# SCART_CONECTOR.net
KiCad netlist of a schematic drawn in EAGLE
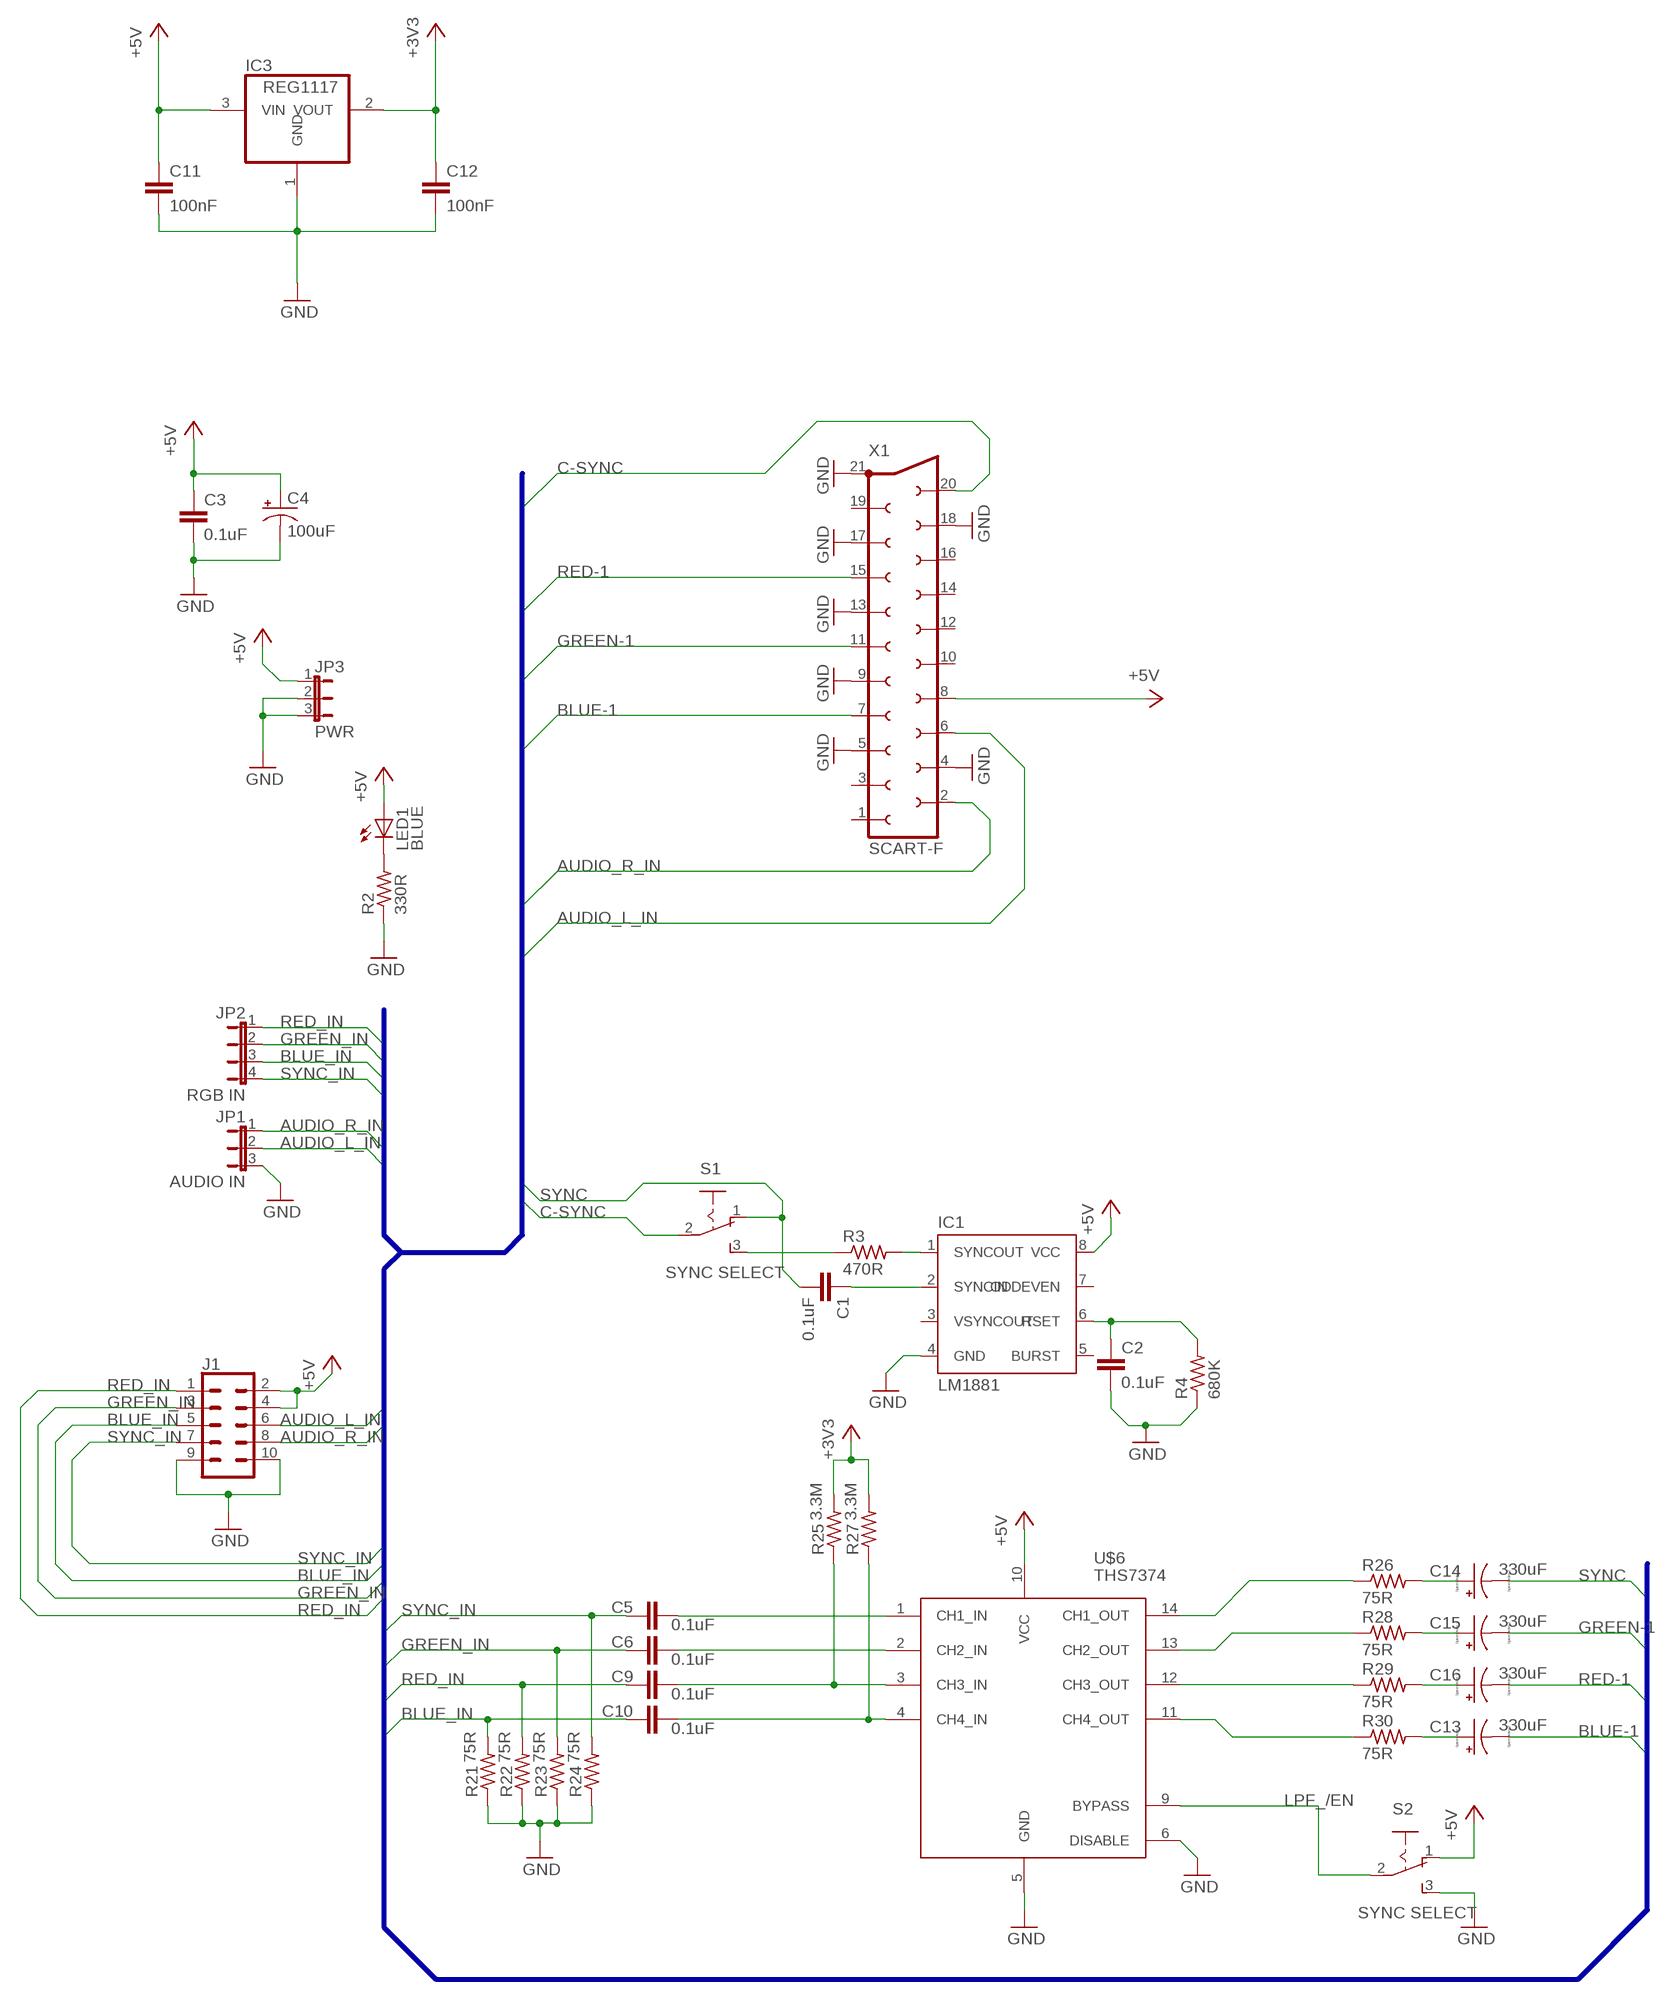
[diagram p0: schematic, sheet 1]

(export (version "E")
  (design (tool "Eeschema 10.0.6"))
  (components
    (comp (ref "C1")
      (value "0.1uF")
      (footprint "eagle-import:C7.5B3")
      (libsource (lib "eagle-import") (part "C7.5/3"))
    )
    (comp (ref "C2")
      (value "0.1uF")
      (footprint "eagle-import:C7.5B3")
      (libsource (lib "eagle-import") (part "C7.5/3"))
    )
    (comp (ref "C3")
      (value "0.1uF")
      (footprint "eagle-import:C7.5B3")
      (libsource (lib "eagle-import") (part "C7.5/3"))
    )
    (comp (ref "C4")
      (value "100uF")
      (footprint "eagle-import:E5-13")
      (libsource (lib "eagle-import") (part "CPOL-USE5-13"))
    )
    (comp (ref "C5")
      (value "0.1uF")
      (footprint "eagle-import:C050-025X075")
      (libsource (lib "eagle-import") (part "C-EU050-025X075"))
    )
    (comp (ref "C6")
      (value "0.1uF")
      (footprint "eagle-import:C050-025X075")
      (libsource (lib "eagle-import") (part "C-EU050-025X075"))
    )
    (comp (ref "C9")
      (value "0.1uF")
      (footprint "eagle-import:C050-025X075")
      (libsource (lib "eagle-import") (part "C-EU050-025X075"))
    )
    (comp (ref "C10")
      (value "0.1uF")
      (footprint "eagle-import:C050-025X075")
      (libsource (lib "eagle-import") (part "C-EU050-025X075"))
    )
    (comp (ref "C11")
      (value "100nF")
      (footprint "eagle-import:C075-032X103")
      (libsource (lib "eagle-import") (part "C-EU075-032X103"))
    )
    (comp (ref "C12")
      (value "100nF")
      (footprint "eagle-import:C075-032X103")
      (libsource (lib "eagle-import") (part "C-EU075-032X103"))
    )
    (comp (ref "C13")
      (value "330uF")
      (footprint "eagle-import:D_7343-31W")
      (libsource (lib "eagle-import") (part "resistor_CPOL-USD/7343-31W"))
    )
    (comp (ref "C14")
      (value "330uF")
      (footprint "eagle-import:D_7343-31W")
      (libsource (lib "eagle-import") (part "resistor_CPOL-USD/7343-31W"))
    )
    (comp (ref "C15")
      (value "330uF")
      (footprint "eagle-import:D_7343-31W")
      (libsource (lib "eagle-import") (part "resistor_CPOL-USD/7343-31W"))
    )
    (comp (ref "C16")
      (value "330uF")
      (footprint "eagle-import:D_7343-31W")
      (libsource (lib "eagle-import") (part "resistor_CPOL-USD/7343-31W"))
    )
    (comp (ref "IC1")
      (value "LM1881")
      (footprint "eagle-import:DIL08")
      (libsource (lib "eagle-import") (part "LM1881"))
    )
    (comp (ref "IC3")
      (value "REG1117")
      (footprint "eagle-import:SOT223")
      (libsource (lib "eagle-import") (part "REG1117"))
    )
    (comp (ref "J1")
      (value "CONN_05X2SHD-NS")
      (footprint "eagle-import:2X5-SHROUDED-NS")
      (libsource (lib "eagle-import") (part "CONN_05X2SHD-NS"))
    )
    (comp (ref "JP1")
      (value "AUDIO IN")
      (footprint "eagle-import:JP2")
      (libsource (lib "eagle-import") (part "JP2E"))
    )
    (comp (ref "JP2")
      (value "RGB IN")
      (footprint "eagle-import:JP4")
      (libsource (lib "eagle-import") (part "JP4E"))
    )
    (comp (ref "JP3")
      (value "PWR")
      (footprint "eagle-import:JP2")
      (libsource (lib "eagle-import") (part "JP2E"))
    )
    (comp (ref "LED1")
      (value "BLUE")
      (footprint "eagle-import:LED5MM")
      (libsource (lib "eagle-import") (part "LED5MM"))
    )
    (comp (ref "R2")
      (value "330R")
      (footprint "eagle-import:0204_7")
      (libsource (lib "eagle-import") (part "R-US_0204/7"))
    )
    (comp (ref "R3")
      (value "470R")
      (footprint "eagle-import:0204_7")
      (libsource (lib "eagle-import") (part "R-US_0204/7"))
    )
    (comp (ref "R4")
      (value "680K")
      (footprint "eagle-import:0204_7")
      (libsource (lib "eagle-import") (part "R-US_0204/7"))
    )
    (comp (ref "R21")
      (value "75R")
      (footprint "eagle-import:0204V")
      (libsource (lib "eagle-import") (part "R-US_0204/2V"))
    )
    (comp (ref "R22")
      (value "75R")
      (footprint "eagle-import:0204V")
      (libsource (lib "eagle-import") (part "R-US_0204/2V"))
    )
    (comp (ref "R23")
      (value "75R")
      (footprint "eagle-import:0204V")
      (libsource (lib "eagle-import") (part "R-US_0204/2V"))
    )
    (comp (ref "R24")
      (value "75R")
      (footprint "eagle-import:0204V")
      (libsource (lib "eagle-import") (part "R-US_0204/2V"))
    )
    (comp (ref "R25")
      (value "3.3M")
      (footprint "eagle-import:0204_7")
      (libsource (lib "eagle-import") (part "R-US_0204/7"))
    )
    (comp (ref "R26")
      (value "75R")
      (footprint "eagle-import:0204_7")
      (libsource (lib "eagle-import") (part "R-US_0204/7"))
    )
    (comp (ref "R27")
      (value "3.3M")
      (footprint "eagle-import:0204_7")
      (libsource (lib "eagle-import") (part "R-US_0204/7"))
    )
    (comp (ref "R28")
      (value "75R")
      (footprint "eagle-import:0204_7")
      (libsource (lib "eagle-import") (part "R-US_0204/7"))
    )
    (comp (ref "R29")
      (value "75R")
      (footprint "eagle-import:0204_7")
      (libsource (lib "eagle-import") (part "R-US_0204/7"))
    )
    (comp (ref "R30")
      (value "75R")
      (footprint "eagle-import:0204_7")
      (libsource (lib "eagle-import") (part "R-US_0204/7"))
    )
    (comp (ref "S1")
      (value "SYNC SELECT")
      (footprint "eagle-import:255SB")
      (libsource (lib "eagle-import") (part "255SB"))
    )
    (comp (ref "S2")
      (value "SYNC SELECT")
      (footprint "eagle-import:255SB")
      (libsource (lib "eagle-import") (part "255SB"))
    )
    (comp (ref "U$6")
      (value "THS7374")
      (footprint "eagle-import:TSSOP-14")
      (libsource (lib "eagle-import") (part "THS7374"))
    )
    (comp (ref "X1")
      (value "SCART-F")
      (footprint "eagle-import:SCART-F")
      (libsource (lib "eagle-import") (part "SCART-F"))
    )
  )
  (nets
    (net (code "1") (name "+3V3") (class "Default")
      (node (ref "C12") (pin "1") (pinfunction "1_1") (pintype "passive"))
      (node (ref "IC3") (pin "2") (pinfunction "VOUT_2") (pintype "output"))
      (node (ref "R25") (pin "2") (pinfunction "2_2") (pintype "passive"))
      (node (ref "R27") (pin "2") (pinfunction "2_2") (pintype "passive"))
    )
    (net (code "2") (name "+5V") (class "Default")
      (node (ref "C11") (pin "1") (pinfunction "1_1") (pintype "passive"))
      (node (ref "C3") (pin "1") (pinfunction "1_1") (pintype "passive"))
      (node (ref "C4") (pin "+") (pinfunction "+_+") (pintype "passive"))
      (node (ref "IC1") (pin "8") (pinfunction "VCC_8") (pintype "power_in"))
      (node (ref "IC3") (pin "3") (pinfunction "VIN_3") (pintype "input"))
      (node (ref "J1") (pin "2") (pinfunction "2_2") (pintype "passive"))
      (node (ref "J1") (pin "4") (pinfunction "4_4") (pintype "passive"))
      (node (ref "JP3") (pin "1") (pinfunction "1_1") (pintype "passive"))
      (node (ref "LED1") (pin "A") (pinfunction "A_A") (pintype "passive"))
      (node (ref "S2") (pin "1") (pinfunction "O_1") (pintype "passive"))
      (node (ref "U$6") (pin "10") (pinfunction "VCC_10") (pintype "power_in"))
      (node (ref "X1") (pin "8") (pinfunction "8_8") (pintype "passive"))
    )
    (net (code "3") (name "/AUDIO_L_IN") (class "Default")
      (node (ref "J1") (pin "6") (pinfunction "6_6") (pintype "passive"))
      (node (ref "JP1") (pin "2") (pinfunction "2_2") (pintype "passive"))
      (node (ref "X1") (pin "6") (pinfunction "6_6") (pintype "passive"))
    )
    (net (code "4") (name "/AUDIO_R_IN") (class "Default")
      (node (ref "J1") (pin "8") (pinfunction "8_8") (pintype "passive"))
      (node (ref "JP1") (pin "1") (pinfunction "1_1") (pintype "passive"))
      (node (ref "X1") (pin "2") (pinfunction "2_2") (pintype "passive"))
    )
    (net (code "5") (name "/BLUE-1") (class "Default")
      (node (ref "C13") (pin "-") (pinfunction "-_-") (pintype "passive"))
      (node (ref "X1") (pin "7") (pinfunction "7_7") (pintype "passive"))
    )
    (net (code "6") (name "/BLUE_IN") (class "Default")
      (node (ref "C10") (pin "1") (pinfunction "1_1") (pintype "passive"))
      (node (ref "J1") (pin "5") (pinfunction "5_5") (pintype "passive"))
      (node (ref "JP2") (pin "3") (pinfunction "3_3") (pintype "passive"))
      (node (ref "R21") (pin "2") (pinfunction "2_2") (pintype "passive"))
    )
    (net (code "7") (name "/C-SYNC") (class "Default")
      (node (ref "S1") (pin "2") (pinfunction "P_2") (pintype "passive"))
      (node (ref "X1") (pin "20") (pinfunction "20_20") (pintype "passive"))
    )
    (net (code "8") (name "/GREEN-1") (class "Default")
      (node (ref "C15") (pin "-") (pinfunction "-_-") (pintype "passive"))
      (node (ref "X1") (pin "11") (pinfunction "11_11") (pintype "passive"))
    )
    (net (code "9") (name "/GREEN_IN") (class "Default")
      (node (ref "C6") (pin "1") (pinfunction "1_1") (pintype "passive"))
      (node (ref "J1") (pin "3") (pinfunction "3_3") (pintype "passive"))
      (node (ref "JP2") (pin "2") (pinfunction "2_2") (pintype "passive"))
      (node (ref "R23") (pin "2") (pinfunction "2_2") (pintype "passive"))
    )
    (net (code "10") (name "/LPF_{slash}EN") (class "Default")
      (node (ref "S2") (pin "2") (pinfunction "P_2") (pintype "passive"))
      (node (ref "U$6") (pin "9") (pinfunction "BYPASS_9") (pintype "input"))
    )
    (net (code "11") (name "/RED-1") (class "Default")
      (node (ref "C16") (pin "-") (pinfunction "-_-") (pintype "passive"))
      (node (ref "X1") (pin "15") (pinfunction "15_15") (pintype "passive"))
    )
    (net (code "12") (name "/RED_IN") (class "Default")
      (node (ref "C9") (pin "1") (pinfunction "1_1") (pintype "passive"))
      (node (ref "J1") (pin "1") (pinfunction "1_1") (pintype "passive"))
      (node (ref "JP2") (pin "1") (pinfunction "1_1") (pintype "passive"))
      (node (ref "R22") (pin "2") (pinfunction "2_2") (pintype "passive"))
    )
    (net (code "13") (name "/SYNC") (class "Default")
      (node (ref "C1") (pin "2") (pinfunction "2_2") (pintype "passive"))
      (node (ref "C14") (pin "-") (pinfunction "-_-") (pintype "passive"))
      (node (ref "S1") (pin "1") (pinfunction "O_1") (pintype "passive"))
    )
    (net (code "14") (name "/SYNC_IN") (class "Default")
      (node (ref "C5") (pin "1") (pinfunction "1_1") (pintype "passive"))
      (node (ref "J1") (pin "7") (pinfunction "7_7") (pintype "passive"))
      (node (ref "JP2") (pin "4") (pinfunction "4_4") (pintype "passive"))
      (node (ref "R24") (pin "2") (pinfunction "2_2") (pintype "passive"))
    )
    (net (code "15") (name "GND") (class "Default")
      (node (ref "C11") (pin "2") (pinfunction "2_2") (pintype "passive"))
      (node (ref "C12") (pin "2") (pinfunction "2_2") (pintype "passive"))
      (node (ref "C2") (pin "2") (pinfunction "2_2") (pintype "passive"))
      (node (ref "C3") (pin "2") (pinfunction "2_2") (pintype "passive"))
      (node (ref "C4") (pin "-") (pinfunction "-_-") (pintype "passive"))
      (node (ref "IC1") (pin "4") (pinfunction "GND_4") (pintype "power_in"))
      (node (ref "IC3") (pin "1") (pinfunction "GND_1") (pintype "power_in"))
      (node (ref "J1") (pin "10") (pinfunction "10_10") (pintype "passive"))
      (node (ref "J1") (pin "9") (pinfunction "9_9") (pintype "passive"))
      (node (ref "JP1") (pin "3") (pinfunction "3_3") (pintype "passive"))
      (node (ref "JP3") (pin "2") (pinfunction "2_2") (pintype "passive"))
      (node (ref "JP3") (pin "3") (pinfunction "3_3") (pintype "passive"))
      (node (ref "R2") (pin "1") (pinfunction "1_1") (pintype "passive"))
      (node (ref "R21") (pin "1") (pinfunction "1_1") (pintype "passive"))
      (node (ref "R22") (pin "1") (pinfunction "1_1") (pintype "passive"))
      (node (ref "R23") (pin "1") (pinfunction "1_1") (pintype "passive"))
      (node (ref "R24") (pin "1") (pinfunction "1_1") (pintype "passive"))
      (node (ref "R4") (pin "1") (pinfunction "1_1") (pintype "passive"))
      (node (ref "S2") (pin "3") (pinfunction "S_3") (pintype "passive"))
      (node (ref "U$6") (pin "5") (pinfunction "GND_5") (pintype "power_in"))
      (node (ref "U$6") (pin "6") (pinfunction "DISABLE_6") (pintype "input"))
      (node (ref "X1") (pin "13") (pinfunction "13_13") (pintype "passive"))
      (node (ref "X1") (pin "17") (pinfunction "17_17") (pintype "passive"))
      (node (ref "X1") (pin "18") (pinfunction "18_18") (pintype "passive"))
      (node (ref "X1") (pin "21") (pinfunction "21_21") (pintype "passive"))
      (node (ref "X1") (pin "4") (pinfunction "4_4") (pintype "passive"))
      (node (ref "X1") (pin "5") (pinfunction "5_5") (pintype "passive"))
      (node (ref "X1") (pin "9") (pinfunction "9_9") (pintype "passive"))
    )
    (net (code "16") (name "Net-(C13-Pad+)") (class "Default")
      (node (ref "C13") (pin "+") (pinfunction "+_+") (pintype "passive"))
      (node (ref "R30") (pin "2") (pinfunction "2_2") (pintype "passive"))
    )
    (net (code "17") (name "Net-(C14-Pad+)") (class "Default")
      (node (ref "C14") (pin "+") (pinfunction "+_+") (pintype "passive"))
      (node (ref "R26") (pin "2") (pinfunction "2_2") (pintype "passive"))
    )
    (net (code "18") (name "Net-(C15-Pad+)") (class "Default")
      (node (ref "C15") (pin "+") (pinfunction "+_+") (pintype "passive"))
      (node (ref "R28") (pin "2") (pinfunction "2_2") (pintype "passive"))
    )
    (net (code "19") (name "Net-(C16-Pad+)") (class "Default")
      (node (ref "C16") (pin "+") (pinfunction "+_+") (pintype "passive"))
      (node (ref "R29") (pin "2") (pinfunction "2_2") (pintype "passive"))
    )
    (net (code "20") (name "Net-(IC1-RSET)") (class "Default")
      (node (ref "C2") (pin "1") (pinfunction "1_1") (pintype "passive"))
      (node (ref "IC1") (pin "6") (pinfunction "RSET_6") (pintype "output"))
      (node (ref "R4") (pin "2") (pinfunction "2_2") (pintype "passive"))
    )
    (net (code "21") (name "Net-(IC1-SYNCIN)") (class "Default")
      (node (ref "C1") (pin "1") (pinfunction "1_1") (pintype "passive"))
      (node (ref "IC1") (pin "2") (pinfunction "SYNCIN_2") (pintype "input"))
    )
    (net (code "22") (name "Net-(IC1-SYNCOUT)") (class "Default")
      (node (ref "IC1") (pin "1") (pinfunction "SYNCOUT_1") (pintype "output"))
      (node (ref "R3") (pin "2") (pinfunction "2_2") (pintype "passive"))
    )
    (net (code "23") (name "Net-(LED1-C)") (class "Default")
      (node (ref "LED1") (pin "K") (pinfunction "C_K") (pintype "passive"))
      (node (ref "R2") (pin "2") (pinfunction "2_2") (pintype "passive"))
    )
    (net (code "24") (name "Net-(S1-S)") (class "Default")
      (node (ref "R3") (pin "1") (pinfunction "1_1") (pintype "passive"))
      (node (ref "S1") (pin "3") (pinfunction "S_3") (pintype "passive"))
    )
    (net (code "25") (name "Net-(U$6-CH1_IN)") (class "Default")
      (node (ref "C5") (pin "2") (pinfunction "2_2") (pintype "passive"))
      (node (ref "U$6") (pin "1") (pinfunction "CH1_IN_1") (pintype "input"))
    )
    (net (code "26") (name "Net-(U$6-CH1_OUT)") (class "Default")
      (node (ref "R26") (pin "1") (pinfunction "1_1") (pintype "passive"))
      (node (ref "U$6") (pin "14") (pinfunction "CH1_OUT_14") (pintype "output"))
    )
    (net (code "27") (name "Net-(U$6-CH2_IN)") (class "Default")
      (node (ref "C6") (pin "2") (pinfunction "2_2") (pintype "passive"))
      (node (ref "U$6") (pin "2") (pinfunction "CH2_IN_2") (pintype "input"))
    )
    (net (code "28") (name "Net-(U$6-CH2_OUT)") (class "Default")
      (node (ref "R28") (pin "1") (pinfunction "1_1") (pintype "passive"))
      (node (ref "U$6") (pin "13") (pinfunction "CH2_OUT_13") (pintype "output"))
    )
    (net (code "29") (name "Net-(U$6-CH3_IN)") (class "Default")
      (node (ref "C9") (pin "2") (pinfunction "2_2") (pintype "passive"))
      (node (ref "R25") (pin "1") (pinfunction "1_1") (pintype "passive"))
      (node (ref "U$6") (pin "3") (pinfunction "CH3_IN_3") (pintype "input"))
    )
    (net (code "30") (name "Net-(U$6-CH3_OUT)") (class "Default")
      (node (ref "R29") (pin "1") (pinfunction "1_1") (pintype "passive"))
      (node (ref "U$6") (pin "12") (pinfunction "CH3_OUT_12") (pintype "output"))
    )
    (net (code "31") (name "Net-(U$6-CH4_IN)") (class "Default")
      (node (ref "C10") (pin "2") (pinfunction "2_2") (pintype "passive"))
      (node (ref "R27") (pin "1") (pinfunction "1_1") (pintype "passive"))
      (node (ref "U$6") (pin "4") (pinfunction "CH4_IN_4") (pintype "input"))
    )
    (net (code "32") (name "Net-(U$6-CH4_OUT)") (class "Default")
      (node (ref "R30") (pin "1") (pinfunction "1_1") (pintype "passive"))
      (node (ref "U$6") (pin "11") (pinfunction "CH4_OUT_11") (pintype "output"))
    )
    (net (code "33") (name "unconnected-(IC1-BURST-Pad5)") (class "Default")
      (node (ref "IC1") (pin "5") (pinfunction "BURST_5") (pintype "output"))
    )
    (net (code "34") (name "unconnected-(IC1-ODDEVEN-Pad7)") (class "Default")
      (node (ref "IC1") (pin "7") (pinfunction "ODDEVEN_7") (pintype "output"))
    )
    (net (code "35") (name "unconnected-(IC1-VSYNCOUT-Pad3)") (class "Default")
      (node (ref "IC1") (pin "3") (pinfunction "VSYNCOUT_3") (pintype "output"))
    )
    (net (code "36") (name "unconnected-(X1-Pad1)") (class "Default")
      (node (ref "X1") (pin "1") (pinfunction "1_1") (pintype "passive"))
    )
    (net (code "37") (name "unconnected-(X1-Pad3)") (class "Default")
      (node (ref "X1") (pin "3") (pinfunction "3_3") (pintype "passive"))
    )
    (net (code "38") (name "unconnected-(X1-Pad10)") (class "Default")
      (node (ref "X1") (pin "10") (pinfunction "10_10") (pintype "passive"))
    )
    (net (code "39") (name "unconnected-(X1-Pad12)") (class "Default")
      (node (ref "X1") (pin "12") (pinfunction "12_12") (pintype "passive"))
    )
    (net (code "40") (name "unconnected-(X1-Pad14)") (class "Default")
      (node (ref "X1") (pin "14") (pinfunction "14_14") (pintype "passive"))
    )
    (net (code "41") (name "unconnected-(X1-Pad16)") (class "Default")
      (node (ref "X1") (pin "16") (pinfunction "16_16") (pintype "passive"))
    )
    (net (code "42") (name "unconnected-(X1-Pad19)") (class "Default")
      (node (ref "X1") (pin "19") (pinfunction "19_19") (pintype "passive"))
    )
  )
)
